# MCU.net
KiCad netlist of a schematic drawn in Altium Designer
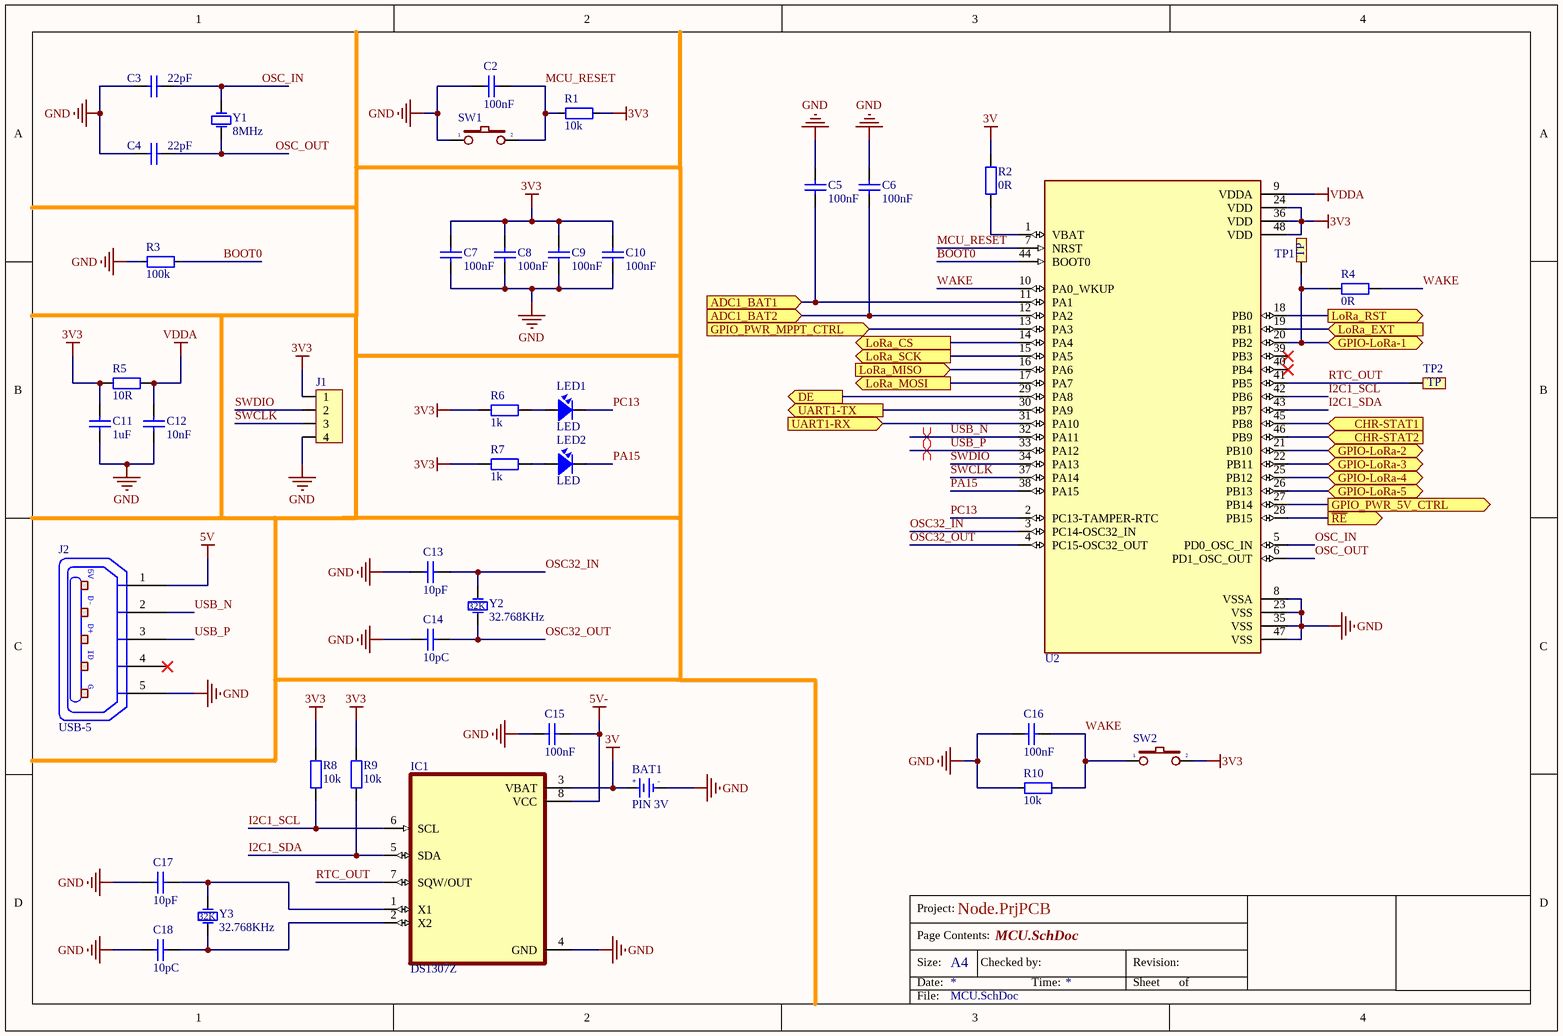
[diagram p0: MCU.SchDoc]

(export (version "E")
  (design (tool "Eeschema 10.0.6"))
  (components
    (comp (ref "BAT1")
      (value "PIN 3V")
      (footprint "CR1220 SMD")
      (description "Battery 3VDC")
      (libsource (lib "My Library") (part "PIN 3V"))
    )
    (comp (ref "C2")
      (value "100nF")
      (footprint "CAP_0805")
      (description "Capacitor")
      (fields (field (name "PUBLISHER") "Altium Limited"))
      (libsource (lib "My Library") (part "CapSMD"))
    )
    (comp (ref "C3")
      (value "22pF")
      (footprint "CAP_0805")
      (description "Capacitor")
      (fields (field (name "PUBLISHER") "Altium Limited"))
      (libsource (lib "My Library") (part "CapSMD"))
    )
    (comp (ref "C4")
      (value "22pF")
      (footprint "CAP_0805")
      (description "Capacitor")
      (fields (field (name "PUBLISHER") "Altium Limited"))
      (libsource (lib "My Library") (part "CapSMD"))
    )
    (comp (ref "C5")
      (value "100nF")
      (footprint "CAP_0805")
      (description "Capacitor")
      (fields (field (name "PUBLISHER") "Altium Limited"))
      (libsource (lib "My Library") (part "CapSMD"))
    )
    (comp (ref "C6")
      (value "100nF")
      (footprint "CAP_0805")
      (description "Capacitor")
      (fields (field (name "PUBLISHER") "Altium Limited"))
      (libsource (lib "My Library") (part "CapSMD"))
    )
    (comp (ref "C7")
      (value "100nF")
      (footprint "CAP_0805")
      (description "Capacitor")
      (fields (field (name "PUBLISHER") "Altium Limited"))
      (libsource (lib "My Library") (part "CapSMD"))
    )
    (comp (ref "C8")
      (value "100nF")
      (footprint "CAP_0805")
      (description "Capacitor")
      (fields (field (name "PUBLISHER") "Altium Limited"))
      (libsource (lib "My Library") (part "CapSMD"))
    )
    (comp (ref "C9")
      (value "100nF")
      (footprint "CAP_0805")
      (description "Capacitor")
      (fields (field (name "PUBLISHER") "Altium Limited"))
      (libsource (lib "My Library") (part "CapSMD"))
    )
    (comp (ref "C10")
      (value "100nF")
      (footprint "CAP_0805")
      (description "Capacitor")
      (fields (field (name "PUBLISHER") "Altium Limited"))
      (libsource (lib "My Library") (part "CapSMD"))
    )
    (comp (ref "C11")
      (value "1uF")
      (footprint "CAP_0805")
      (description "Capacitor")
      (fields (field (name "PUBLISHER") "Altium Limited"))
      (libsource (lib "My Library") (part "CapSMD"))
    )
    (comp (ref "C12")
      (value "10nF")
      (footprint "CAP_0805")
      (description "Capacitor")
      (fields (field (name "PUBLISHER") "Altium Limited"))
      (libsource (lib "My Library") (part "CapSMD"))
    )
    (comp (ref "C13")
      (value "10pF")
      (footprint "CAP_0805")
      (description "Capacitor")
      (fields (field (name "PUBLISHER") "Altium Limited"))
      (libsource (lib "My Library") (part "CapSMD"))
    )
    (comp (ref "C14")
      (value "10pC")
      (footprint "CAP_0805")
      (description "Capacitor")
      (fields (field (name "PUBLISHER") "Altium Limited"))
      (libsource (lib "My Library") (part "CapSMD"))
    )
    (comp (ref "C15")
      (value "100nF")
      (footprint "CAP_0805")
      (description "Capacitor")
      (fields (field (name "PUBLISHER") "Altium Limited"))
      (libsource (lib "My Library") (part "CapSMD"))
    )
    (comp (ref "C16")
      (value "100nF")
      (footprint "CAP_0805")
      (description "Capacitor")
      (fields (field (name "PUBLISHER") "Altium Limited"))
      (libsource (lib "My Library") (part "CapSMD"))
    )
    (comp (ref "C17")
      (value "10pF")
      (footprint "CAP_0805")
      (description "Capacitor")
      (fields (field (name "PUBLISHER") "Altium Limited"))
      (libsource (lib "My Library") (part "CapSMD"))
    )
    (comp (ref "C18")
      (value "10pC")
      (footprint "CAP_0805")
      (description "Capacitor")
      (fields (field (name "PUBLISHER") "Altium Limited"))
      (libsource (lib "My Library") (part "CapSMD"))
    )
    (comp (ref "IC1") (value "DS1307Z") (footprint "SOIC-8") (libsource (lib "My Library") (part "DS1307Z")))
    (comp (ref "J1")
      (value "ST_Link")
      (footprint "HEADER4P-1.25")
      (description "Header IDC, 4 x 1 Pin Vertical 2.54mm Pitch (Non-Boxed, Male)")
      (fields
        (field (name "MANUFACTURER") "Würth Elektronik eiSos GmbH")
        (field (name "PARTNO") "613002143121")
        (field (name "CREATED BY") "Karrer Zheng")
      )
      (libsource (lib "My Library") (part "Header4"))
    )
    (comp (ref "J2")
      (value "USB-5")
      (footprint "USB-M1")
      (fields
        (field (name "MANUFACTURER") "FCI")
        (field (name "MANUFACTURER PART NUMBER") "10118193-0001LF")
        (field (name ".CREATOR") "MM")
        (field (name ".CHECKED PCB") "RF")
        (field (name ".CHECKED SCH") "MM")
      )
      (libsource (lib "My Library") (part "USB-5"))
    )
    (comp (ref "LED1")
      (value "LED")
      (footprint "LED-0805-Red")
      (description "LED Single colour Green and Red")
      (libsource (lib "My Library") (part "LED"))
    )
    (comp (ref "LED2")
      (value "LED")
      (footprint "LED-0805-Yellow")
      (description "LED Single colour Green and Red")
      (libsource (lib "My Library") (part "LED"))
    )
    (comp (ref "R1")
      (value "10k")
      (footprint "RES-SMD-0805")
      (description "Resistor")
      (fields
        (field (name "MANUFACTURER") "Generic Components")
        (field (name "PUBLISHER") "Altium Hobart Technology Centre")
      )
      (libsource (lib "") (part "Resistor - SMD_1"))
    )
    (comp (ref "R2")
      (value "0R")
      (footprint "RES-SMD-0805")
      (description "Resistor SMD")
      (fields
        (field (name "MANUFACTURER") "Generic Components")
        (field (name "PUBLISHER") "Altium Hobart Technology Centre")
      )
      (libsource (lib "My Library") (part "Resistor - SMD"))
    )
    (comp (ref "R3")
      (value "100k")
      (footprint "RES-SMD-0805")
      (description "Resistor")
      (fields
        (field (name "MANUFACTURER") "Generic Components")
        (field (name "PUBLISHER") "Altium Hobart Technology Centre")
      )
      (libsource (lib "") (part "Resistor - SMD_1"))
    )
    (comp (ref "R4")
      (value "0R")
      (footprint "RES-SMD-0805")
      (description "Resistor SMD")
      (fields
        (field (name "MANUFACTURER") "Generic Components")
        (field (name "PUBLISHER") "Altium Hobart Technology Centre")
      )
      (libsource (lib "My Library") (part "Resistor - SMD"))
    )
    (comp (ref "R5")
      (value "10R")
      (footprint "RES-SMD-0805")
      (description "Resistor SMD")
      (fields
        (field (name "MANUFACTURER") "Generic Components")
        (field (name "PUBLISHER") "Altium Hobart Technology Centre")
      )
      (libsource (lib "My Library") (part "Resistor - SMD"))
    )
    (comp (ref "R6")
      (value "1k")
      (footprint "RES-SMD-0805")
      (description "Resistor SMD")
      (fields
        (field (name "MANUFACTURER") "Generic Components")
        (field (name "PUBLISHER") "Altium Hobart Technology Centre")
      )
      (libsource (lib "My Library") (part "Resistor - SMD"))
    )
    (comp (ref "R7")
      (value "1k")
      (footprint "RES-SMD-0805")
      (description "Resistor SMD")
      (fields
        (field (name "MANUFACTURER") "Generic Components")
        (field (name "PUBLISHER") "Altium Hobart Technology Centre")
      )
      (libsource (lib "My Library") (part "Resistor - SMD"))
    )
    (comp (ref "R8")
      (value "10k")
      (footprint "RES-SMD-0805")
      (description "Resistor SMD")
      (fields
        (field (name "MANUFACTURER") "Generic Components")
        (field (name "PUBLISHER") "Altium Hobart Technology Centre")
      )
      (libsource (lib "My Library") (part "Resistor - SMD"))
    )
    (comp (ref "R9")
      (value "10k")
      (footprint "RES-SMD-0805")
      (description "Resistor SMD")
      (fields
        (field (name "MANUFACTURER") "Generic Components")
        (field (name "PUBLISHER") "Altium Hobart Technology Centre")
      )
      (libsource (lib "My Library") (part "Resistor - SMD"))
    )
    (comp (ref "R10")
      (value "10k")
      (footprint "RES-SMD-0805")
      (description "Resistor")
      (fields
        (field (name "MANUFACTURER") "Generic Components")
        (field (name "PUBLISHER") "Altium Hobart Technology Centre")
      )
      (libsource (lib "") (part "Resistor - SMD_1"))
    )
    (comp (ref "SW1")
      (value "SW")
      (footprint "SW 3x2x4")
      (description "Switch button 2 pin")
      (libsource (lib "My Library") (part "SW2"))
    )
    (comp (ref "SW2")
      (value "SW")
      (footprint "SW 3x2x4")
      (description "Switch button 2 pin")
      (libsource (lib "My Library") (part "SW2"))
    )
    (comp (ref "TP1")
      (value "Test Point")
      (footprint "TP_SMD")
      (description "CONNECT 1")
      (libsource (lib "") (part "TP_1"))
    )
    (comp (ref "TP2")
      (value "Test Point")
      (footprint "TP_SMD")
      (description "CONNECT 1")
      (libsource (lib "My Library") (part "TP"))
    )
    (comp (ref "U2")
      (value "STM32")
      (footprint "LQFP 48")
      (description "STM32 ARM-based 32-bit MCU with 64 Kbytes Flash, 64-pin LQFP, Industrial Temperature")
      (libsource (lib "Ven_lib") (part "STM32F103C8T6"))
    )
    (comp (ref "Y1")
      (value "8MHz")
      (footprint "XTAL")
      (description "Crystal Oscillator")
      (fields (field (name "PUBLISHER") "Altium Limited"))
      (libsource (lib "My Library") (part "XTAL"))
    )
    (comp (ref "Y2")
      (value "32.768KHz")
      (footprint "XTAL32K")
      (description "Crystal Oscillator")
      (fields (field (name "PUBLISHER") "Altium Limited"))
      (libsource (lib "My Library") (part "XTAL/32KHz"))
    )
    (comp (ref "Y3")
      (value "32.768KHz")
      (footprint "XTAL32K")
      (description "Crystal Oscillator")
      (fields (field (name "PUBLISHER") "Altium Limited"))
      (libsource (lib "My Library") (part "XTAL/32KHz"))
    )
  )
  (nets
    (net (code "1") (name "/ADC1_BAT1") (class "Default")
      (node (ref "C5") (pin "1") (pinfunction "1_1") (pintype "passive"))
      (node (ref "U2") (pin "11") (pinfunction "PA1_11") (pintype "bidirectional"))
    )
    (net (code "2") (name "/ADC1_BAT2") (class "Default")
      (node (ref "C6") (pin "1") (pinfunction "1_1") (pintype "passive"))
      (node (ref "U2") (pin "12") (pinfunction "PA2_12") (pintype "bidirectional"))
    )
    (net (code "3") (name "/BOOT0") (class "Default")
      (node (ref "R3") (pin "1") (pinfunction "1_1") (pintype "passive"))
      (node (ref "U2") (pin "44") (pinfunction "BOOT0_44") (pintype "input"))
    )
    (net (code "4") (name "/CHR-STAT1") (class "Default")
      (node (ref "U2") (pin "45") (pinfunction "PB8_45") (pintype "bidirectional"))
    )
    (net (code "5") (name "/CHR-STAT2") (class "Default")
      (node (ref "U2") (pin "46") (pinfunction "PB9_46") (pintype "bidirectional"))
    )
    (net (code "6") (name "/DE") (class "Default")
      (node (ref "U2") (pin "29") (pinfunction "PA8_29") (pintype "bidirectional"))
    )
    (net (code "7") (name "/GPIO-LoRa-1") (class "Default")
      (node (ref "R4") (pin "2") (pinfunction "2_2") (pintype "passive"))
      (node (ref "TP1") (pin "1") (pinfunction "0_1") (pintype "passive"))
      (node (ref "U2") (pin "20") (pinfunction "PB2_20") (pintype "bidirectional"))
    )
    (net (code "8") (name "/GPIO-LoRa-2") (class "Default")
      (node (ref "U2") (pin "21") (pinfunction "PB10_21") (pintype "bidirectional"))
    )
    (net (code "9") (name "/GPIO-LoRa-3") (class "Default")
      (node (ref "U2") (pin "22") (pinfunction "PB11_22") (pintype "bidirectional"))
    )
    (net (code "10") (name "/GPIO-LoRa-4") (class "Default")
      (node (ref "U2") (pin "25") (pinfunction "PB12_25") (pintype "bidirectional"))
    )
    (net (code "11") (name "/GPIO-LoRa-5") (class "Default")
      (node (ref "U2") (pin "26") (pinfunction "PB13_26") (pintype "bidirectional"))
    )
    (net (code "12") (name "/GPIO_PWR_5V_CTRL") (class "Default")
      (node (ref "U2") (pin "27") (pinfunction "PB14_27") (pintype "bidirectional"))
    )
    (net (code "13") (name "/GPIO_PWR_MPPT_CTRL") (class "Default")
      (node (ref "U2") (pin "13") (pinfunction "PA3_13") (pintype "bidirectional"))
    )
    (net (code "14") (name "/I2C1_SCL") (class "Default")
      (node (ref "IC1") (pin "6") (pinfunction "SCL_6") (pintype "input"))
      (node (ref "R8") (pin "1") (pinfunction "1_1") (pintype "passive"))
      (node (ref "U2") (pin "42") (pinfunction "PB6_42") (pintype "bidirectional"))
    )
    (net (code "15") (name "/I2C1_SDA") (class "Default")
      (node (ref "IC1") (pin "5") (pinfunction "SDA_5") (pintype "bidirectional"))
      (node (ref "R9") (pin "1") (pinfunction "1_1") (pintype "passive"))
      (node (ref "U2") (pin "43") (pinfunction "PB7_43") (pintype "bidirectional"))
    )
    (net (code "16") (name "/LoRa_CS") (class "Default")
      (node (ref "U2") (pin "14") (pinfunction "PA4_14") (pintype "bidirectional"))
    )
    (net (code "17") (name "/LoRa_EXT") (class "Default")
      (node (ref "U2") (pin "19") (pinfunction "PB1_19") (pintype "bidirectional"))
    )
    (net (code "18") (name "/LoRa_MISO") (class "Default")
      (node (ref "U2") (pin "16") (pinfunction "PA6_16") (pintype "bidirectional"))
    )
    (net (code "19") (name "/LoRa_MOSI") (class "Default")
      (node (ref "U2") (pin "17") (pinfunction "PA7_17") (pintype "bidirectional"))
    )
    (net (code "20") (name "/LoRa_RST") (class "Default")
      (node (ref "U2") (pin "18") (pinfunction "PB0_18") (pintype "bidirectional"))
    )
    (net (code "21") (name "/LoRa_SCK") (class "Default")
      (node (ref "U2") (pin "15") (pinfunction "PA5_15") (pintype "bidirectional"))
    )
    (net (code "22") (name "/MCU_RESET") (class "Default")
      (node (ref "C2") (pin "2") (pinfunction "2_2") (pintype "passive"))
      (node (ref "R1") (pin "2") (pinfunction "2_2") (pintype "passive"))
      (node (ref "SW1") (pin "2") (pinfunction "2_2") (pintype "passive"))
      (node (ref "U2") (pin "7") (pinfunction "NRST_7") (pintype "input"))
    )
    (net (code "23") (name "/OSC32_IN") (class "Default")
      (node (ref "C13") (pin "1") (pinfunction "1_1") (pintype "passive"))
      (node (ref "U2") (pin "3") (pinfunction "PC14-OSC32_IN_3") (pintype "bidirectional"))
      (node (ref "Y2") (pin "1") (pinfunction "OSC1_1") (pintype "passive"))
    )
    (net (code "24") (name "/OSC32_OUT") (class "Default")
      (node (ref "C14") (pin "1") (pinfunction "1_1") (pintype "passive"))
      (node (ref "U2") (pin "4") (pinfunction "PC15-OSC32_OUT_4") (pintype "bidirectional"))
      (node (ref "Y2") (pin "2") (pinfunction "OSC2_2") (pintype "passive"))
    )
    (net (code "25") (name "/OSC_IN") (class "Default")
      (node (ref "C3") (pin "2") (pinfunction "2_2") (pintype "passive"))
      (node (ref "U2") (pin "5") (pinfunction "PD0_OSC_IN_5") (pintype "bidirectional"))
      (node (ref "Y1") (pin "1") (pinfunction "OSC1_1") (pintype "passive"))
    )
    (net (code "26") (name "/OSC_OUT") (class "Default")
      (node (ref "C4") (pin "2") (pinfunction "2_2") (pintype "passive"))
      (node (ref "U2") (pin "6") (pinfunction "PD1_OSC_OUT_6") (pintype "bidirectional"))
      (node (ref "Y1") (pin "2") (pinfunction "OSC2_2") (pintype "passive"))
    )
    (net (code "27") (name "/PA15") (class "Default")
      (node (ref "LED2") (pin "2") (pinfunction "2_2") (pintype "passive"))
      (node (ref "U2") (pin "38") (pinfunction "PA15_38") (pintype "bidirectional"))
    )
    (net (code "28") (name "/PC13") (class "Default")
      (node (ref "LED1") (pin "2") (pinfunction "2_2") (pintype "passive"))
      (node (ref "U2") (pin "2") (pinfunction "PC13-TAMPER-RTC_2") (pintype "bidirectional"))
    )
    (net (code "29") (name "/RTC_OUT") (class "Default")
      (node (ref "IC1") (pin "7") (pinfunction "SQW/OUT_7") (pintype "bidirectional"))
      (node (ref "TP2") (pin "1") (pinfunction "0_1") (pintype "passive"))
      (node (ref "U2") (pin "41") (pinfunction "PB5_41") (pintype "bidirectional"))
    )
    (net (code "30") (name "/SWCLK") (class "Default")
      (node (ref "J1") (pin "3") (pinfunction "3_3") (pintype "passive"))
      (node (ref "U2") (pin "37") (pinfunction "PA14_37") (pintype "bidirectional"))
    )
    (net (code "31") (name "/SWDIO") (class "Default")
      (node (ref "J1") (pin "2") (pinfunction "2_2") (pintype "passive"))
      (node (ref "U2") (pin "34") (pinfunction "PA13_34") (pintype "bidirectional"))
    )
    (net (code "32") (name "/UART1-RX") (class "Default")
      (node (ref "U2") (pin "31") (pinfunction "PA10_31") (pintype "bidirectional"))
    )
    (net (code "33") (name "/UART1-TX") (class "Default")
      (node (ref "U2") (pin "30") (pinfunction "PA9_30") (pintype "bidirectional"))
    )
    (net (code "34") (name "/USB_N") (class "Default")
      (node (ref "J2") (pin "2") (pinfunction "P2_2") (pintype "passive"))
      (node (ref "U2") (pin "32") (pinfunction "PA11_32") (pintype "bidirectional"))
    )
    (net (code "35") (name "/USB_P") (class "Default")
      (node (ref "J2") (pin "3") (pinfunction "P3_3") (pintype "passive"))
      (node (ref "U2") (pin "33") (pinfunction "PA12_33") (pintype "bidirectional"))
    )
    (net (code "36") (name "/WAKE") (class "Default")
      (node (ref "C16") (pin "2") (pinfunction "2_2") (pintype "passive"))
      (node (ref "R10") (pin "1") (pinfunction "1_1") (pintype "passive"))
      (node (ref "R4") (pin "1") (pinfunction "1_1") (pintype "passive"))
      (node (ref "SW2") (pin "1") (pinfunction "1_1") (pintype "passive"))
      (node (ref "U2") (pin "10") (pinfunction "PA0_WKUP_10") (pintype "bidirectional"))
    )
    (net (code "37") (name "/~{RE}") (class "Default")
      (node (ref "U2") (pin "28") (pinfunction "PB15_28") (pintype "bidirectional"))
    )
    (net (code "38") (name "3V") (class "Default")
      (node (ref "BAT1") (pin "1") (pinfunction "+3V_1") (pintype "passive"))
      (node (ref "IC1") (pin "3") (pinfunction "VBAT_3") (pintype "power_in"))
      (node (ref "R2") (pin "2") (pinfunction "2_2") (pintype "passive"))
    )
    (net (code "39") (name "3V3") (class "Default")
      (node (ref "C10") (pin "2") (pinfunction "2_2") (pintype "passive"))
      (node (ref "C11") (pin "2") (pinfunction "2_2") (pintype "passive"))
      (node (ref "C7") (pin "2") (pinfunction "2_2") (pintype "passive"))
      (node (ref "C8") (pin "2") (pinfunction "2_2") (pintype "passive"))
      (node (ref "C9") (pin "2") (pinfunction "2_2") (pintype "passive"))
      (node (ref "J1") (pin "1") (pinfunction "1_1") (pintype "passive"))
      (node (ref "R1") (pin "1") (pinfunction "1_1") (pintype "passive"))
      (node (ref "R5") (pin "1") (pinfunction "1_1") (pintype "passive"))
      (node (ref "R6") (pin "1") (pinfunction "1_1") (pintype "passive"))
      (node (ref "R7") (pin "1") (pinfunction "1_1") (pintype "passive"))
      (node (ref "R8") (pin "2") (pinfunction "2_2") (pintype "passive"))
      (node (ref "R9") (pin "2") (pinfunction "2_2") (pintype "passive"))
      (node (ref "SW2") (pin "2") (pinfunction "2_2") (pintype "passive"))
      (node (ref "U2") (pin "24") (pinfunction "VDD_24") (pintype "power_in"))
      (node (ref "U2") (pin "36") (pinfunction "VDD_36") (pintype "power_in"))
      (node (ref "U2") (pin "48") (pinfunction "VDD_48") (pintype "power_in"))
    )
    (net (code "40") (name "5V") (class "Default")
      (node (ref "J2") (pin "1") (pinfunction "P1_1") (pintype "passive"))
    )
    (net (code "41") (name "5V-") (class "Default")
      (node (ref "C15") (pin "2") (pinfunction "2_2") (pintype "passive"))
      (node (ref "IC1") (pin "8") (pinfunction "VCC_8") (pintype "power_in"))
    )
    (net (code "42") (name "GND") (class "Default")
      (node (ref "BAT1") (pin "2") (pinfunction "GND_2") (pintype "passive"))
      (node (ref "C10") (pin "1") (pinfunction "1_1") (pintype "passive"))
      (node (ref "C11") (pin "1") (pinfunction "1_1") (pintype "passive"))
      (node (ref "C12") (pin "1") (pinfunction "1_1") (pintype "passive"))
      (node (ref "C13") (pin "2") (pinfunction "2_2") (pintype "passive"))
      (node (ref "C14") (pin "2") (pinfunction "2_2") (pintype "passive"))
      (node (ref "C15") (pin "1") (pinfunction "1_1") (pintype "passive"))
      (node (ref "C16") (pin "1") (pinfunction "1_1") (pintype "passive"))
      (node (ref "C17") (pin "2") (pinfunction "2_2") (pintype "passive"))
      (node (ref "C18") (pin "2") (pinfunction "2_2") (pintype "passive"))
      (node (ref "C2") (pin "1") (pinfunction "1_1") (pintype "passive"))
      (node (ref "C3") (pin "1") (pinfunction "1_1") (pintype "passive"))
      (node (ref "C4") (pin "1") (pinfunction "1_1") (pintype "passive"))
      (node (ref "C5") (pin "2") (pinfunction "2_2") (pintype "passive"))
      (node (ref "C6") (pin "2") (pinfunction "2_2") (pintype "passive"))
      (node (ref "C7") (pin "1") (pinfunction "1_1") (pintype "passive"))
      (node (ref "C8") (pin "1") (pinfunction "1_1") (pintype "passive"))
      (node (ref "C9") (pin "1") (pinfunction "1_1") (pintype "passive"))
      (node (ref "IC1") (pin "4") (pinfunction "GND_4") (pintype "power_in"))
      (node (ref "J1") (pin "4") (pinfunction "4_4") (pintype "passive"))
      (node (ref "J2") (pin "5") (pinfunction "P5_5") (pintype "passive"))
      (node (ref "R10") (pin "2") (pinfunction "2_2") (pintype "passive"))
      (node (ref "R3") (pin "2") (pinfunction "2_2") (pintype "passive"))
      (node (ref "SW1") (pin "1") (pinfunction "1_1") (pintype "passive"))
      (node (ref "U2") (pin "23") (pinfunction "VSS_23") (pintype "power_in"))
      (node (ref "U2") (pin "35") (pinfunction "VSS_35") (pintype "power_in"))
      (node (ref "U2") (pin "47") (pinfunction "VSS_47") (pintype "power_in"))
      (node (ref "U2") (pin "8") (pinfunction "VSSA_8") (pintype "power_in"))
    )
    (net (code "43") (name "Net-(IC1-X1)") (class "Default")
      (node (ref "C17") (pin "1") (pinfunction "1_1") (pintype "passive"))
      (node (ref "IC1") (pin "1") (pinfunction "X1_1") (pintype "bidirectional"))
      (node (ref "Y3") (pin "1") (pinfunction "OSC1_1") (pintype "passive"))
    )
    (net (code "44") (name "Net-(IC1-X2)") (class "Default")
      (node (ref "C18") (pin "1") (pinfunction "1_1") (pintype "passive"))
      (node (ref "IC1") (pin "2") (pinfunction "X2_2") (pintype "bidirectional"))
      (node (ref "Y3") (pin "2") (pinfunction "OSC2_2") (pintype "passive"))
    )
    (net (code "45") (name "Net-(LED1-Pad1)") (class "Default")
      (node (ref "LED1") (pin "1") (pinfunction "1_1") (pintype "passive"))
      (node (ref "R6") (pin "2") (pinfunction "2_2") (pintype "passive"))
    )
    (net (code "46") (name "Net-(LED2-Pad1)") (class "Default")
      (node (ref "LED2") (pin "1") (pinfunction "1_1") (pintype "passive"))
      (node (ref "R7") (pin "2") (pinfunction "2_2") (pintype "passive"))
    )
    (net (code "47") (name "Net-(U2-VBAT)") (class "Default")
      (node (ref "R2") (pin "1") (pinfunction "1_1") (pintype "passive"))
      (node (ref "U2") (pin "1") (pinfunction "VBAT_1") (pintype "bidirectional"))
    )
    (net (code "48") (name "VDDA") (class "Default")
      (node (ref "C12") (pin "2") (pinfunction "2_2") (pintype "passive"))
      (node (ref "R5") (pin "2") (pinfunction "2_2") (pintype "passive"))
      (node (ref "U2") (pin "9") (pinfunction "VDDA_9") (pintype "power_in"))
    )
    (net (code "49") (name "unconnected-(J2-P4-Pad4)") (class "Default")
      (node (ref "J2") (pin "4") (pinfunction "P4_4") (pintype "passive+no_connect"))
    )
    (net (code "50") (name "unconnected-(U2-PB3-Pad39)") (class "Default")
      (node (ref "U2") (pin "39") (pinfunction "PB3_39") (pintype "bidirectional+no_connect"))
    )
    (net (code "51") (name "unconnected-(U2-PB4-Pad40)") (class "Default")
      (node (ref "U2") (pin "40") (pinfunction "PB4_40") (pintype "bidirectional+no_connect"))
    )
  )
)
